# esp8266_v4_test.net
KiCad netlist of a schematic drawn in EAGLE
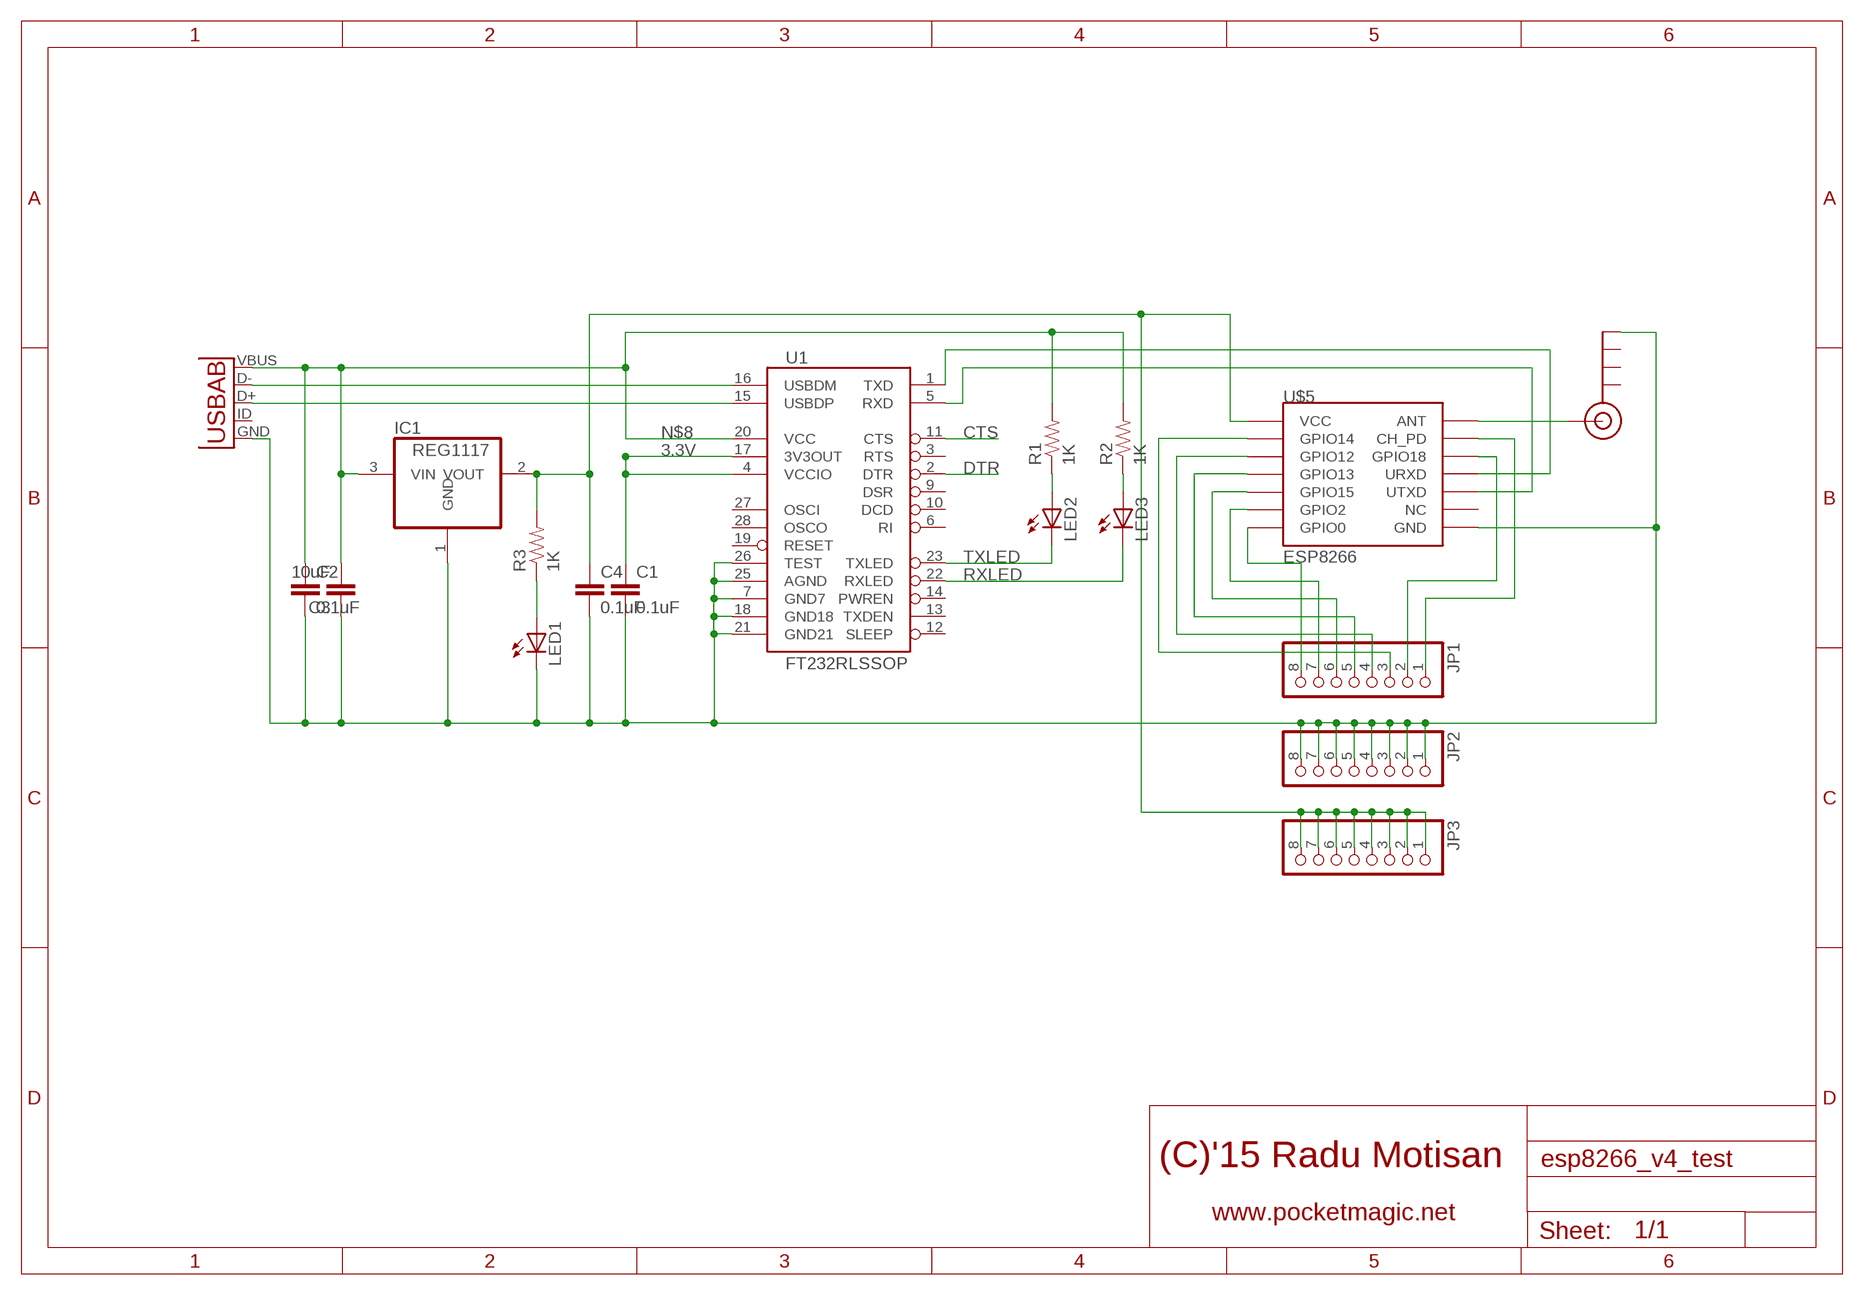
[diagram p0: schematic, sheet 1]

(export (version "E")
  (design (tool "Eeschema 10.0.6"))
  (components
    (comp (ref "C1")
      (value "0.1uF")
      (footprint "eagle-import:0805")
      (libsource (lib "eagle-import") (part "CAP0805"))
    )
    (comp (ref "C2")
      (value "0.1uF")
      (footprint "eagle-import:0805")
      (libsource (lib "eagle-import") (part "CAP0805"))
    )
    (comp (ref "C3")
      (value "10uF")
      (footprint "eagle-import:C0805K")
      (libsource (lib "eagle-import") (part "C-EUC0805K"))
    )
    (comp (ref "C4")
      (value "0.1uF")
      (footprint "eagle-import:0805")
      (libsource (lib "eagle-import") (part "CAP0805"))
    )
    (comp (ref "IC1")
      (value "REG1117")
      (footprint "eagle-import:SOT223")
      (libsource (lib "eagle-import") (part "REG1117"))
    )
    (comp (ref "J$1")
      (value "SMA_EDGE")
      (footprint "eagle-import:SMA-EDGE")
      (libsource (lib "eagle-import") (part "SMA_EDGE"))
    )
    (comp (ref "JP1")
      (value "PINHD-1X8CLEANBIG")
      (footprint "eagle-import:1X08-CLEANBIG")
      (libsource (lib "eagle-import") (part "PINHD-1X8CLEANBIG"))
    )
    (comp (ref "JP2")
      (value "PINHD-1X8CLEANBIG")
      (footprint "eagle-import:1X08-CLEANBIG")
      (libsource (lib "eagle-import") (part "PINHD-1X8CLEANBIG"))
    )
    (comp (ref "JP3")
      (value "PINHD-1X8CLEANBIG")
      (footprint "eagle-import:1X08-CLEANBIG")
      (libsource (lib "eagle-import") (part "PINHD-1X8CLEANBIG"))
    )
    (comp (ref "LED1")
      (value "LEDCHIP-LED0805")
      (footprint "eagle-import:CHIP-LED0805")
      (libsource (lib "eagle-import") (part "LEDCHIP-LED0805"))
    )
    (comp (ref "LED2")
      (value "LEDCHIP-LED0805")
      (footprint "eagle-import:CHIP-LED0805")
      (libsource (lib "eagle-import") (part "LEDCHIP-LED0805"))
    )
    (comp (ref "LED3")
      (value "LEDCHIP-LED0805")
      (footprint "eagle-import:CHIP-LED0805")
      (libsource (lib "eagle-import") (part "LEDCHIP-LED0805"))
    )
    (comp (ref "R1")
      (value "1K")
      (footprint "eagle-import:0805")
      (libsource (lib "eagle-import") (part "RESISTOR0805-RES"))
    )
    (comp (ref "R2")
      (value "1K")
      (footprint "eagle-import:0805")
      (libsource (lib "eagle-import") (part "RESISTOR0805-RES"))
    )
    (comp (ref "R3")
      (value "1K")
      (footprint "eagle-import:0805")
      (libsource (lib "eagle-import") (part "RESISTOR0805-RES"))
    )
    (comp (ref "U$2")
      (value "USB_AB")
      (footprint "eagle-import:USB-AB-MICRO-SMD")
      (libsource (lib "eagle-import") (part "USB_AB"))
    )
    (comp (ref "U$5")
      (value "ESP8266")
      (footprint "eagle-import:ESP-03")
      (libsource (lib "eagle-import") (part "ESP8266"))
    )
    (comp (ref "U1")
      (value "FT232RLSSOP")
      (footprint "eagle-import:SSOP28DB")
      (libsource (lib "eagle-import") (part "FT232RLSSOP"))
    )
  )
  (nets
    (net (code "1") (name "/3.3V") (class "Default")
      (node (ref "C1") (pin "1") (pinfunction "1_1") (pintype "passive"))
      (node (ref "U1") (pin "17") (pinfunction "3V3OUT_17") (pintype "output"))
      (node (ref "U1") (pin "4") (pinfunction "VCCIO_4") (pintype "power_in"))
    )
    (net (code "2") (name "/CTS") (class "Default")
      (node (ref "U1") (pin "11") (pinfunction "CTS_11") (pintype "input"))
    )
    (net (code "3") (name "/DTR") (class "Default")
      (node (ref "U1") (pin "2") (pinfunction "DTR_2") (pintype "output"))
    )
    (net (code "4") (name "/N$8") (class "Default")
      (node (ref "C2") (pin "1") (pinfunction "1_1") (pintype "passive"))
      (node (ref "C3") (pin "2") (pinfunction "2_2") (pintype "passive"))
      (node (ref "IC1") (pin "3") (pinfunction "VIN_3") (pintype "input"))
      (node (ref "R1") (pin "2") (pinfunction "2_2") (pintype "passive"))
      (node (ref "R2") (pin "2") (pinfunction "2_2") (pintype "passive"))
      (node (ref "U$2") (pin "VBUS") (pinfunction "VBUS_VBUS") (pintype "bidirectional"))
      (node (ref "U1") (pin "20") (pinfunction "VCC_20") (pintype "power_in"))
    )
    (net (code "5") (name "/RXLED") (class "Default")
      (node (ref "LED3") (pin "C") (pinfunction "C_C") (pintype "passive"))
      (node (ref "U1") (pin "22") (pinfunction "RXLED_22") (pintype "input"))
    )
    (net (code "6") (name "/TXLED") (class "Default")
      (node (ref "LED2") (pin "C") (pinfunction "C_C") (pintype "passive"))
      (node (ref "U1") (pin "23") (pinfunction "TXLED_23") (pintype "input"))
    )
    (net (code "7") (name "Net-(IC1-GND)") (class "Default")
      (node (ref "C1") (pin "2") (pinfunction "2_2") (pintype "passive"))
      (node (ref "C2") (pin "2") (pinfunction "2_2") (pintype "passive"))
      (node (ref "C3") (pin "1") (pinfunction "1_1") (pintype "passive"))
      (node (ref "C4") (pin "2") (pinfunction "2_2") (pintype "passive"))
      (node (ref "IC1") (pin "1") (pinfunction "GND_1") (pintype "power_in"))
      (node (ref "J$1") (pin "GND@3") (pinfunction "GND_GND@3") (pintype "bidirectional"))
      (node (ref "JP2") (pin "1") (pinfunction "1_1") (pintype "passive"))
      (node (ref "JP2") (pin "2") (pinfunction "2_2") (pintype "passive"))
      (node (ref "JP2") (pin "3") (pinfunction "3_3") (pintype "passive"))
      (node (ref "JP2") (pin "4") (pinfunction "4_4") (pintype "passive"))
      (node (ref "JP2") (pin "5") (pinfunction "5_5") (pintype "passive"))
      (node (ref "JP2") (pin "6") (pinfunction "6_6") (pintype "passive"))
      (node (ref "JP2") (pin "7") (pinfunction "7_7") (pintype "passive"))
      (node (ref "JP2") (pin "8") (pinfunction "8_8") (pintype "passive"))
      (node (ref "LED1") (pin "C") (pinfunction "C_C") (pintype "passive"))
      (node (ref "U$2") (pin "GND") (pinfunction "GND_GND") (pintype "bidirectional"))
      (node (ref "U$5") (pin "GND") (pinfunction "GND_GND") (pintype "bidirectional"))
      (node (ref "U1") (pin "18") (pinfunction "GND18_18") (pintype "power_in"))
      (node (ref "U1") (pin "21") (pinfunction "GND21_21") (pintype "power_in"))
      (node (ref "U1") (pin "25") (pinfunction "AGND_25") (pintype "power_in"))
      (node (ref "U1") (pin "26") (pinfunction "TEST_26") (pintype "input"))
      (node (ref "U1") (pin "7") (pinfunction "GND7_7") (pintype "power_in"))
    )
    (net (code "8") (name "Net-(IC1-VOUT)") (class "Default")
      (node (ref "C4") (pin "1") (pinfunction "1_1") (pintype "passive"))
      (node (ref "IC1") (pin "2") (pinfunction "VOUT_2") (pintype "output"))
      (node (ref "JP3") (pin "1") (pinfunction "1_1") (pintype "passive"))
      (node (ref "JP3") (pin "2") (pinfunction "2_2") (pintype "passive"))
      (node (ref "JP3") (pin "3") (pinfunction "3_3") (pintype "passive"))
      (node (ref "JP3") (pin "4") (pinfunction "4_4") (pintype "passive"))
      (node (ref "JP3") (pin "5") (pinfunction "5_5") (pintype "passive"))
      (node (ref "JP3") (pin "6") (pinfunction "6_6") (pintype "passive"))
      (node (ref "JP3") (pin "7") (pinfunction "7_7") (pintype "passive"))
      (node (ref "JP3") (pin "8") (pinfunction "8_8") (pintype "passive"))
      (node (ref "R3") (pin "2") (pinfunction "2_2") (pintype "passive"))
      (node (ref "U$5") (pin "VCC") (pinfunction "VCC_VCC") (pintype "bidirectional"))
    )
    (net (code "9") (name "Net-(J$1-SIGNAL)") (class "Default")
      (node (ref "J$1") (pin "SIG") (pinfunction "SIGNAL_SIG") (pintype "bidirectional"))
      (node (ref "U$5") (pin "ANT") (pinfunction "ANT_ANT") (pintype "bidirectional"))
    )
    (net (code "10") (name "Net-(JP1-Pad1)") (class "Default")
      (node (ref "JP1") (pin "1") (pinfunction "1_1") (pintype "passive"))
      (node (ref "U$5") (pin "CH_PD") (pinfunction "CH_PD_CH_PD") (pintype "bidirectional"))
    )
    (net (code "11") (name "Net-(JP1-Pad2)") (class "Default")
      (node (ref "JP1") (pin "2") (pinfunction "2_2") (pintype "passive"))
      (node (ref "U$5") (pin "GPIO18") (pinfunction "GPIO18_GPIO18") (pintype "bidirectional"))
    )
    (net (code "12") (name "Net-(JP1-Pad3)") (class "Default")
      (node (ref "JP1") (pin "3") (pinfunction "3_3") (pintype "passive"))
      (node (ref "U$5") (pin "GPIO14") (pinfunction "GPIO14_GPIO14") (pintype "bidirectional"))
    )
    (net (code "13") (name "Net-(JP1-Pad4)") (class "Default")
      (node (ref "JP1") (pin "4") (pinfunction "4_4") (pintype "passive"))
      (node (ref "U$5") (pin "GPIO12") (pinfunction "GPIO12_GPIO12") (pintype "bidirectional"))
    )
    (net (code "14") (name "Net-(JP1-Pad5)") (class "Default")
      (node (ref "JP1") (pin "5") (pinfunction "5_5") (pintype "passive"))
      (node (ref "U$5") (pin "GPIO13") (pinfunction "GPIO13_GPIO13") (pintype "bidirectional"))
    )
    (net (code "15") (name "Net-(JP1-Pad6)") (class "Default")
      (node (ref "JP1") (pin "6") (pinfunction "6_6") (pintype "passive"))
      (node (ref "U$5") (pin "GPIO15") (pinfunction "GPIO15_GPIO15") (pintype "bidirectional"))
    )
    (net (code "16") (name "Net-(JP1-Pad7)") (class "Default")
      (node (ref "JP1") (pin "7") (pinfunction "7_7") (pintype "passive"))
      (node (ref "U$5") (pin "GPIO2") (pinfunction "GPIO2_GPIO2") (pintype "bidirectional"))
    )
    (net (code "17") (name "Net-(JP1-Pad8)") (class "Default")
      (node (ref "JP1") (pin "8") (pinfunction "8_8") (pintype "passive"))
      (node (ref "U$5") (pin "GPIO0") (pinfunction "GPIO0_GPIO0") (pintype "bidirectional"))
    )
    (net (code "18") (name "Net-(LED1-PadA)") (class "Default")
      (node (ref "LED1") (pin "A") (pinfunction "A_A") (pintype "passive"))
      (node (ref "R3") (pin "1") (pinfunction "1_1") (pintype "passive"))
    )
    (net (code "19") (name "Net-(LED2-PadA)") (class "Default")
      (node (ref "LED2") (pin "A") (pinfunction "A_A") (pintype "passive"))
      (node (ref "R1") (pin "1") (pinfunction "1_1") (pintype "passive"))
    )
    (net (code "20") (name "Net-(LED3-PadA)") (class "Default")
      (node (ref "LED3") (pin "A") (pinfunction "A_A") (pintype "passive"))
      (node (ref "R2") (pin "1") (pinfunction "1_1") (pintype "passive"))
    )
    (net (code "21") (name "Net-(U1-RXD)") (class "Default")
      (node (ref "U$5") (pin "UTXD") (pinfunction "UTXD_UTXD") (pintype "bidirectional"))
      (node (ref "U1") (pin "5") (pinfunction "RXD_5") (pintype "input"))
    )
    (net (code "22") (name "Net-(U1-TXD)") (class "Default")
      (node (ref "U$5") (pin "URXD") (pinfunction "URXD_URXD") (pintype "bidirectional"))
      (node (ref "U1") (pin "1") (pinfunction "TXD_1") (pintype "output"))
    )
    (net (code "23") (name "Net-(U1-USBDM)") (class "Default")
      (node (ref "U$2") (pin "D-") (pinfunction "D-_D-") (pintype "bidirectional"))
      (node (ref "U1") (pin "16") (pinfunction "USBDM_16") (pintype "bidirectional"))
    )
    (net (code "24") (name "Net-(U1-USBDP)") (class "Default")
      (node (ref "U$2") (pin "D+") (pinfunction "D+_D+") (pintype "bidirectional"))
      (node (ref "U1") (pin "15") (pinfunction "USBDP_15") (pintype "bidirectional"))
    )
    (net (code "25") (name "unconnected-(J$1-GND-PadGND@0)") (class "Default")
      (node (ref "J$1") (pin "GND@0") (pinfunction "GND_GND@0") (pintype "bidirectional"))
    )
    (net (code "26") (name "unconnected-(J$1-GND-PadGND@1)") (class "Default")
      (node (ref "J$1") (pin "GND@1") (pinfunction "GND_GND@1") (pintype "bidirectional"))
    )
    (net (code "27") (name "unconnected-(J$1-GND-PadGND@2)") (class "Default")
      (node (ref "J$1") (pin "GND@2") (pinfunction "GND_GND@2") (pintype "bidirectional"))
    )
    (net (code "28") (name "unconnected-(U$2-USBID-PadID)") (class "Default")
      (node (ref "U$2") (pin "ID") (pinfunction "USBID_ID") (pintype "bidirectional"))
    )
    (net (code "29") (name "unconnected-(U$5-PadNC)") (class "Default")
      (node (ref "U$5") (pin "NC") (pinfunction "NC_NC") (pintype "bidirectional"))
    )
    (net (code "30") (name "unconnected-(U1-DCD-Pad10)") (class "Default")
      (node (ref "U1") (pin "10") (pinfunction "DCD_10") (pintype "input"))
    )
    (net (code "31") (name "unconnected-(U1-DSR-Pad9)") (class "Default")
      (node (ref "U1") (pin "9") (pinfunction "DSR_9") (pintype "input"))
    )
    (net (code "32") (name "unconnected-(U1-OSCI-Pad27)") (class "Default")
      (node (ref "U1") (pin "27") (pinfunction "OSCI_27") (pintype "input"))
    )
    (net (code "33") (name "unconnected-(U1-OSCO-Pad28)") (class "Default")
      (node (ref "U1") (pin "28") (pinfunction "OSCO_28") (pintype "output"))
    )
    (net (code "34") (name "unconnected-(U1-PWREN-Pad14)") (class "Default")
      (node (ref "U1") (pin "14") (pinfunction "PWREN_14") (pintype "input"))
    )
    (net (code "35") (name "unconnected-(U1-RESET-Pad19)") (class "Default")
      (node (ref "U1") (pin "19") (pinfunction "RESET_19") (pintype "input"))
    )
    (net (code "36") (name "unconnected-(U1-RI-Pad6)") (class "Default")
      (node (ref "U1") (pin "6") (pinfunction "RI_6") (pintype "input"))
    )
    (net (code "37") (name "unconnected-(U1-RTS-Pad3)") (class "Default")
      (node (ref "U1") (pin "3") (pinfunction "RTS_3") (pintype "output"))
    )
    (net (code "38") (name "unconnected-(U1-SLEEP-Pad12)") (class "Default")
      (node (ref "U1") (pin "12") (pinfunction "SLEEP_12") (pintype "input"))
    )
    (net (code "39") (name "unconnected-(U1-TXDEN-Pad13)") (class "Default")
      (node (ref "U1") (pin "13") (pinfunction "TXDEN_13") (pintype "input"))
    )
  )
)
